# QED_2550_dos_caras.net
KiCad netlist of a schematic drawn in EAGLE
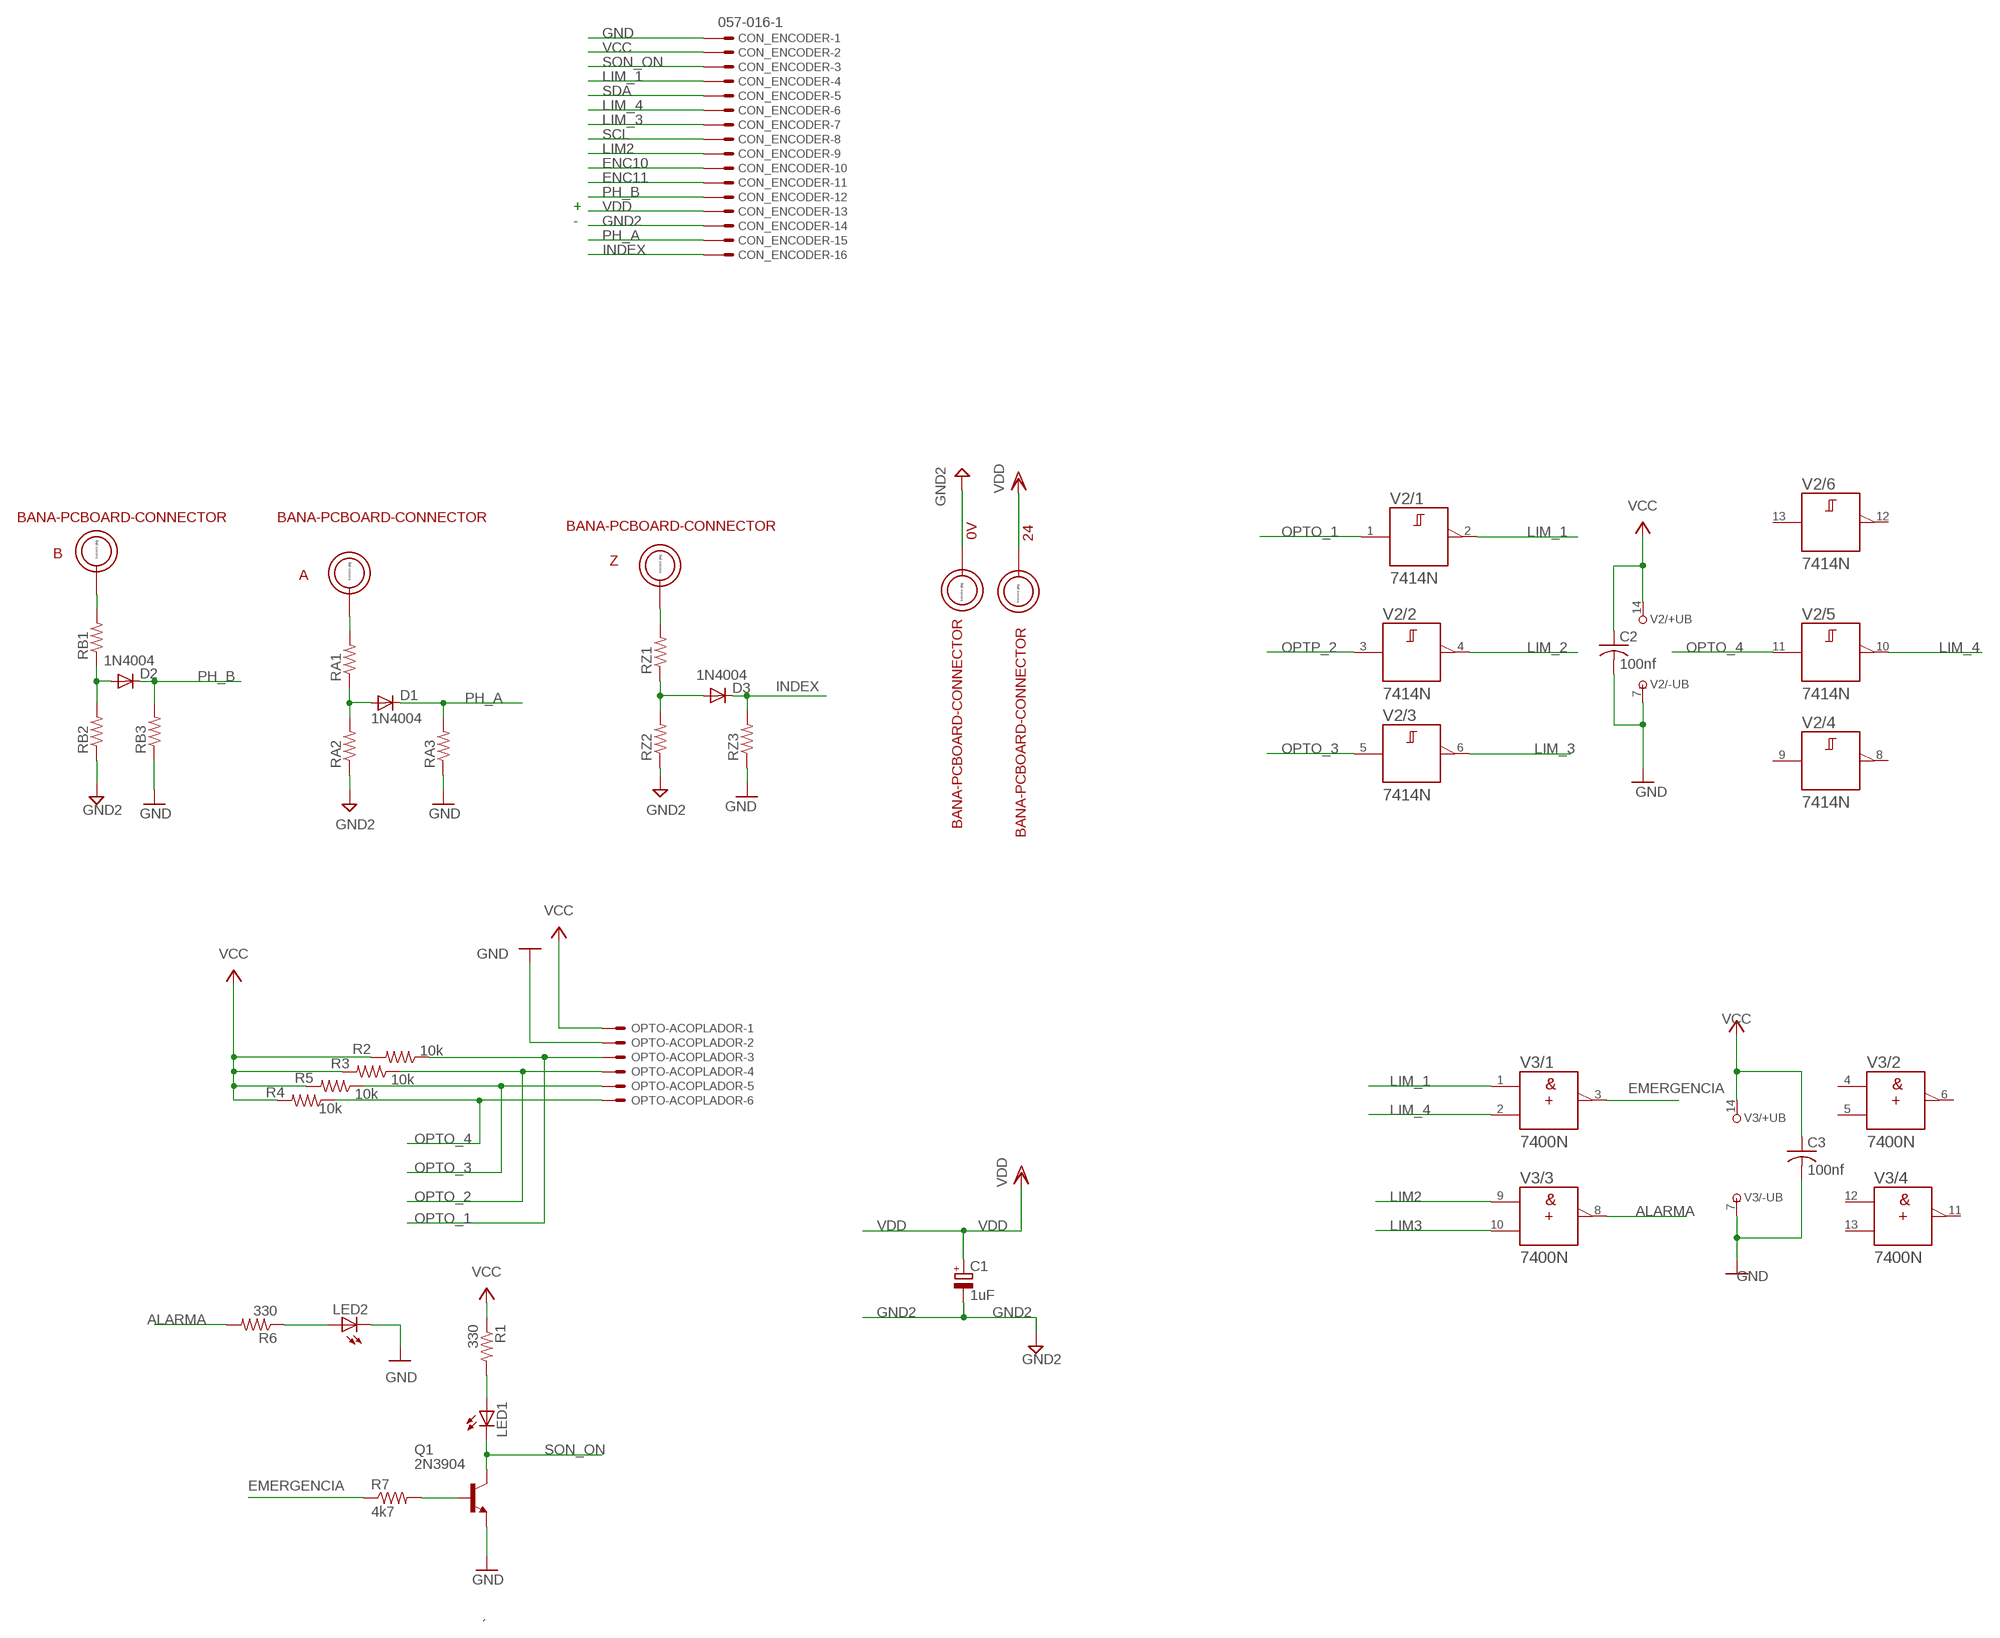
[diagram p0: schematic, sheet 1]

(export (version "E")
  (design (tool "Eeschema 10.0.6"))
  (components
    (comp (ref "0V")
      (value "BANA-PCBOARD-CONNECTOR")
      (footprint "eagle-import:BANA_PLUG")
      (libsource (lib "eagle-import") (part "BANA-PCBOARD-CONNECTOR"))
    )
    (comp (ref "24")
      (value "BANA-PCBOARD-CONNECTOR")
      (footprint "eagle-import:BANA_PLUG")
      (libsource (lib "eagle-import") (part "BANA-PCBOARD-CONNECTOR"))
    )
    (comp (ref "A")
      (value "BANA-PCBOARD-CONNECTOR")
      (footprint "eagle-import:BANA_PLUG")
      (libsource (lib "eagle-import") (part "BANA-PCBOARD-CONNECTOR"))
    )
    (comp (ref "B")
      (value "BANA-PCBOARD-CONNECTOR")
      (footprint "eagle-import:BANA_PLUG")
      (libsource (lib "eagle-import") (part "BANA-PCBOARD-CONNECTOR"))
    )
    (comp (ref "C1")
      (value "1uF")
      (footprint "eagle-import:E2,5-6")
      (libsource (lib "eagle-import") (part "CPOL-EUE2.5-6"))
    )
    (comp (ref "C2")
      (value "100nf")
      (footprint "eagle-import:C025-024X044")
      (libsource (lib "eagle-import") (part "C-US025-024X044"))
    )
    (comp (ref "C3")
      (value "100nf")
      (footprint "eagle-import:C025-024X044")
      (libsource (lib "eagle-import") (part "C-US025-024X044"))
    )
    (comp (ref "CON_ENCODER")
      (value "057-016-1")
      (footprint "eagle-import:057-016-1")
      (libsource (lib "eagle-import") (part "057-016-1"))
    )
    (comp (ref "D1")
      (value "1N4004")
      (footprint "eagle-import:DO41-10")
      (libsource (lib "eagle-import") (part "1N4004"))
    )
    (comp (ref "D2")
      (value "1N4004")
      (footprint "eagle-import:DO41-10")
      (libsource (lib "eagle-import") (part "1N4004"))
    )
    (comp (ref "D3")
      (value "1N4004")
      (footprint "eagle-import:DO41-10")
      (libsource (lib "eagle-import") (part "1N4004"))
    )
    (comp (ref "LED1")
      (value "LED5MM")
      (footprint "eagle-import:LED5MM")
      (libsource (lib "eagle-import") (part "LED5MM"))
    )
    (comp (ref "LED2")
      (value "LED5MM")
      (footprint "eagle-import:LED5MM")
      (libsource (lib "eagle-import") (part "LED5MM"))
    )
    (comp (ref "OPTO-ACOPLADOR")
      (value "22-23-2061")
      (footprint "eagle-import:22-23-2061")
      (fields (field (name "MF") "MOLEX"))
      (libsource (lib "eagle-import") (part "22-23-2061"))
    )
    (comp (ref "Q1")
      (value "2N3904")
      (footprint "eagle-import:TO92")
      (libsource (lib "eagle-import") (part "2N3904"))
    )
    (comp (ref "R1")
      (value "330")
      (footprint "eagle-import:0204_7")
      (libsource (lib "eagle-import") (part "R-US_0204/7"))
    )
    (comp (ref "R2")
      (value "10k")
      (footprint "eagle-import:0204_7")
      (libsource (lib "eagle-import") (part "R-US_0204/7"))
    )
    (comp (ref "R3")
      (value "10k")
      (footprint "eagle-import:0204_7")
      (libsource (lib "eagle-import") (part "R-US_0204/7"))
    )
    (comp (ref "R4")
      (value "10k")
      (footprint "eagle-import:0204_7")
      (libsource (lib "eagle-import") (part "R-US_0204/7"))
    )
    (comp (ref "R5")
      (value "10k")
      (footprint "eagle-import:0204_7")
      (libsource (lib "eagle-import") (part "R-US_0204/7"))
    )
    (comp (ref "R6")
      (value "330")
      (footprint "eagle-import:0204_7")
      (libsource (lib "eagle-import") (part "R-US_0204/7"))
    )
    (comp (ref "R7")
      (value "4k7")
      (footprint "eagle-import:0204_7")
      (libsource (lib "eagle-import") (part "R-US_0204/7"))
    )
    (comp (ref "RA1")
      (value "R-US_0204/7")
      (footprint "eagle-import:0204_7")
      (libsource (lib "eagle-import") (part "R-US_0204/7"))
    )
    (comp (ref "RA2")
      (value "R-US_0204/7")
      (footprint "eagle-import:0204_7")
      (libsource (lib "eagle-import") (part "R-US_0204/7"))
    )
    (comp (ref "RA3")
      (value "R-US_0204/7")
      (footprint "eagle-import:0204_7")
      (libsource (lib "eagle-import") (part "R-US_0204/7"))
    )
    (comp (ref "RB1")
      (value "R-US_0204/7")
      (footprint "eagle-import:0204_7")
      (libsource (lib "eagle-import") (part "R-US_0204/7"))
    )
    (comp (ref "RB2")
      (value "R-US_0204/7")
      (footprint "eagle-import:0204_7")
      (libsource (lib "eagle-import") (part "R-US_0204/7"))
    )
    (comp (ref "RB3")
      (value "R-US_0204/7")
      (footprint "eagle-import:0204_7")
      (libsource (lib "eagle-import") (part "R-US_0204/7"))
    )
    (comp (ref "RZ1")
      (value "R-US_0204/7")
      (footprint "eagle-import:0204_7")
      (libsource (lib "eagle-import") (part "R-US_0204/7"))
    )
    (comp (ref "RZ2")
      (value "R-US_0204/7")
      (footprint "eagle-import:0204_7")
      (libsource (lib "eagle-import") (part "R-US_0204/7"))
    )
    (comp (ref "RZ3")
      (value "R-US_0204/7")
      (footprint "eagle-import:0204_7")
      (libsource (lib "eagle-import") (part "R-US_0204/7"))
    )
    (comp (ref "V2")
      (value "7414N")
      (footprint "eagle-import:DIL14")
      (libsource (lib "eagle-import") (part "7414N"))
    )
    (comp (ref "V3")
      (value "7400N")
      (footprint "eagle-import:DIL14")
      (libsource (lib "eagle-import") (part "7400N"))
    )
    (comp (ref "Z")
      (value "BANA-PCBOARD-CONNECTOR")
      (footprint "eagle-import:BANA_PLUG")
      (libsource (lib "eagle-import") (part "BANA-PCBOARD-CONNECTOR"))
    )
  )
  (nets
    (net (code "1") (name "/ALARMA") (class "Default")
      (node (ref "R6") (pin "2") (pinfunction "2_2") (pintype "passive"))
      (node (ref "V3") (pin "8") (pinfunction "Y_8") (pintype "output"))
    )
    (net (code "2") (name "/EMERGENCIA") (class "Default")
      (node (ref "R7") (pin "1") (pinfunction "1_1") (pintype "passive"))
      (node (ref "V3") (pin "3") (pinfunction "Y_3") (pintype "output"))
    )
    (net (code "3") (name "/ENC10") (class "Default")
      (node (ref "CON_ENCODER") (pin "10") (pinfunction "S_10") (pintype "passive"))
    )
    (net (code "4") (name "/ENC11") (class "Default")
      (node (ref "CON_ENCODER") (pin "11") (pinfunction "S_11") (pintype "passive"))
    )
    (net (code "5") (name "/INDEX") (class "Default")
      (node (ref "CON_ENCODER") (pin "16") (pinfunction "S_16") (pintype "passive"))
      (node (ref "D3") (pin "C") (pinfunction "C_C") (pintype "passive"))
      (node (ref "RZ3") (pin "2") (pinfunction "2_2") (pintype "passive"))
    )
    (net (code "6") (name "/LIM2") (class "Default")
      (node (ref "CON_ENCODER") (pin "9") (pinfunction "S_9") (pintype "passive"))
      (node (ref "V3") (pin "9") (pinfunction "A_9") (pintype "input"))
    )
    (net (code "7") (name "/LIM3") (class "Default")
      (node (ref "V3") (pin "10") (pinfunction "B_10") (pintype "input"))
    )
    (net (code "8") (name "/LIM_1") (class "Default")
      (node (ref "CON_ENCODER") (pin "4") (pinfunction "S_4") (pintype "passive"))
      (node (ref "V2") (pin "2") (pinfunction "Y_2") (pintype "output"))
      (node (ref "V3") (pin "1") (pinfunction "A_1") (pintype "input"))
    )
    (net (code "9") (name "/LIM_2") (class "Default")
      (node (ref "V2") (pin "4") (pinfunction "Y_4") (pintype "output"))
    )
    (net (code "10") (name "/LIM_3") (class "Default")
      (node (ref "CON_ENCODER") (pin "7") (pinfunction "S_7") (pintype "passive"))
      (node (ref "V2") (pin "6") (pinfunction "Y_6") (pintype "output"))
    )
    (net (code "11") (name "/LIM_4") (class "Default")
      (node (ref "CON_ENCODER") (pin "6") (pinfunction "S_6") (pintype "passive"))
      (node (ref "V2") (pin "10") (pinfunction "Y_10") (pintype "output"))
      (node (ref "V3") (pin "2") (pinfunction "B_2") (pintype "input"))
    )
    (net (code "12") (name "/OPTO_1") (class "Default")
      (node (ref "OPTO-ACOPLADOR") (pin "3") (pinfunction "S_3") (pintype "passive"))
      (node (ref "R2") (pin "1") (pinfunction "1_1") (pintype "passive"))
      (node (ref "V2") (pin "1") (pinfunction "A_1") (pintype "input"))
    )
    (net (code "13") (name "/OPTO_2") (class "Default")
      (node (ref "OPTO-ACOPLADOR") (pin "4") (pinfunction "S_4") (pintype "passive"))
      (node (ref "R3") (pin "1") (pinfunction "1_1") (pintype "passive"))
    )
    (net (code "14") (name "/OPTO_3") (class "Default")
      (node (ref "OPTO-ACOPLADOR") (pin "5") (pinfunction "S_5") (pintype "passive"))
      (node (ref "R5") (pin "1") (pinfunction "1_1") (pintype "passive"))
      (node (ref "V2") (pin "5") (pinfunction "A_5") (pintype "input"))
    )
    (net (code "15") (name "/OPTO_4") (class "Default")
      (node (ref "OPTO-ACOPLADOR") (pin "6") (pinfunction "S_6") (pintype "passive"))
      (node (ref "R4") (pin "1") (pinfunction "1_1") (pintype "passive"))
      (node (ref "V2") (pin "11") (pinfunction "A_11") (pintype "input"))
    )
    (net (code "16") (name "/OPTP_2") (class "Default")
      (node (ref "V2") (pin "3") (pinfunction "A_3") (pintype "input"))
    )
    (net (code "17") (name "/PH_A") (class "Default")
      (node (ref "CON_ENCODER") (pin "15") (pinfunction "S_15") (pintype "passive"))
      (node (ref "D1") (pin "C") (pinfunction "C_C") (pintype "passive"))
      (node (ref "RA3") (pin "2") (pinfunction "2_2") (pintype "passive"))
    )
    (net (code "18") (name "/PH_B") (class "Default")
      (node (ref "CON_ENCODER") (pin "12") (pinfunction "S_12") (pintype "passive"))
      (node (ref "D2") (pin "C") (pinfunction "C_C") (pintype "passive"))
      (node (ref "RB3") (pin "2") (pinfunction "2_2") (pintype "passive"))
    )
    (net (code "19") (name "/SCL") (class "Default")
      (node (ref "CON_ENCODER") (pin "8") (pinfunction "S_8") (pintype "passive"))
    )
    (net (code "20") (name "/SDA") (class "Default")
      (node (ref "CON_ENCODER") (pin "5") (pinfunction "S_5") (pintype "passive"))
    )
    (net (code "21") (name "/SON_ON") (class "Default")
      (node (ref "CON_ENCODER") (pin "3") (pinfunction "S_3") (pintype "passive"))
      (node (ref "LED1") (pin "K") (pinfunction "C_K") (pintype "passive"))
      (node (ref "Q1") (pin "1") (pinfunction "C_1") (pintype "passive"))
    )
    (net (code "22") (name "GND") (class "Default")
      (node (ref "C2") (pin "2") (pinfunction "2_2") (pintype "passive"))
      (node (ref "C3") (pin "2") (pinfunction "2_2") (pintype "passive"))
      (node (ref "CON_ENCODER") (pin "1") (pinfunction "S_1") (pintype "passive"))
      (node (ref "LED2") (pin "K") (pinfunction "C_K") (pintype "passive"))
      (node (ref "OPTO-ACOPLADOR") (pin "2") (pinfunction "S_2") (pintype "passive"))
      (node (ref "Q1") (pin "3") (pinfunction "E_3") (pintype "passive"))
      (node (ref "RA3") (pin "1") (pinfunction "1_1") (pintype "passive"))
      (node (ref "RB3") (pin "1") (pinfunction "1_1") (pintype "passive"))
      (node (ref "RZ3") (pin "1") (pinfunction "1_1") (pintype "passive"))
      (node (ref "V2") (pin "7") (pinfunction "-UB_7") (pintype "power_in"))
      (node (ref "V3") (pin "7") (pinfunction "-UB_7") (pintype "power_in"))
    )
    (net (code "23") (name "GND2") (class "Default")
      (node (ref "0V") (pin "P$1") (pinfunction "P$1_P$1") (pintype "bidirectional"))
      (node (ref "C1") (pin "-") (pinfunction "-_-") (pintype "passive"))
      (node (ref "CON_ENCODER") (pin "14") (pinfunction "S_14") (pintype "passive"))
      (node (ref "RA2") (pin "1") (pinfunction "1_1") (pintype "passive"))
      (node (ref "RB2") (pin "1") (pinfunction "1_1") (pintype "passive"))
      (node (ref "RZ2") (pin "1") (pinfunction "1_1") (pintype "passive"))
    )
    (net (code "24") (name "Net-(A-PadP$1)") (class "Default")
      (node (ref "A") (pin "P$1") (pinfunction "P$1_P$1") (pintype "bidirectional"))
      (node (ref "RA1") (pin "2") (pinfunction "2_2") (pintype "passive"))
    )
    (net (code "25") (name "Net-(B-PadP$1)") (class "Default")
      (node (ref "B") (pin "P$1") (pinfunction "P$1_P$1") (pintype "bidirectional"))
      (node (ref "RB1") (pin "2") (pinfunction "2_2") (pintype "passive"))
    )
    (net (code "26") (name "Net-(D1-PadA)") (class "Default")
      (node (ref "D1") (pin "A") (pinfunction "A_A") (pintype "passive"))
      (node (ref "RA1") (pin "1") (pinfunction "1_1") (pintype "passive"))
      (node (ref "RA2") (pin "2") (pinfunction "2_2") (pintype "passive"))
    )
    (net (code "27") (name "Net-(D2-PadA)") (class "Default")
      (node (ref "D2") (pin "A") (pinfunction "A_A") (pintype "passive"))
      (node (ref "RB1") (pin "1") (pinfunction "1_1") (pintype "passive"))
      (node (ref "RB2") (pin "2") (pinfunction "2_2") (pintype "passive"))
    )
    (net (code "28") (name "Net-(D3-PadA)") (class "Default")
      (node (ref "D3") (pin "A") (pinfunction "A_A") (pintype "passive"))
      (node (ref "RZ1") (pin "1") (pinfunction "1_1") (pintype "passive"))
      (node (ref "RZ2") (pin "2") (pinfunction "2_2") (pintype "passive"))
    )
    (net (code "29") (name "Net-(LED1-PadA)") (class "Default")
      (node (ref "LED1") (pin "A") (pinfunction "A_A") (pintype "passive"))
      (node (ref "R1") (pin "2") (pinfunction "2_2") (pintype "passive"))
    )
    (net (code "30") (name "Net-(LED2-PadA)") (class "Default")
      (node (ref "LED2") (pin "A") (pinfunction "A_A") (pintype "passive"))
      (node (ref "R6") (pin "1") (pinfunction "1_1") (pintype "passive"))
    )
    (net (code "31") (name "Net-(Q1-B)") (class "Default")
      (node (ref "Q1") (pin "2") (pinfunction "B_2") (pintype "passive"))
      (node (ref "R7") (pin "2") (pinfunction "2_2") (pintype "passive"))
    )
    (net (code "32") (name "Net-(RZ1-Pad2)") (class "Default")
      (node (ref "RZ1") (pin "2") (pinfunction "2_2") (pintype "passive"))
      (node (ref "Z") (pin "P$1") (pinfunction "P$1_P$1") (pintype "bidirectional"))
    )
    (net (code "33") (name "VCC") (class "Default")
      (node (ref "C2") (pin "1") (pinfunction "1_1") (pintype "passive"))
      (node (ref "C3") (pin "1") (pinfunction "1_1") (pintype "passive"))
      (node (ref "CON_ENCODER") (pin "2") (pinfunction "S_2") (pintype "passive"))
      (node (ref "OPTO-ACOPLADOR") (pin "1") (pinfunction "S_1") (pintype "passive"))
      (node (ref "R1") (pin "1") (pinfunction "1_1") (pintype "passive"))
      (node (ref "R2") (pin "2") (pinfunction "2_2") (pintype "passive"))
      (node (ref "R3") (pin "2") (pinfunction "2_2") (pintype "passive"))
      (node (ref "R4") (pin "2") (pinfunction "2_2") (pintype "passive"))
      (node (ref "R5") (pin "2") (pinfunction "2_2") (pintype "passive"))
      (node (ref "V2") (pin "14") (pinfunction "+UB_14") (pintype "power_in"))
      (node (ref "V3") (pin "14") (pinfunction "+UB_14") (pintype "power_in"))
    )
    (net (code "34") (name "VDD") (class "Default")
      (node (ref "24") (pin "P$1") (pinfunction "P$1_P$1") (pintype "bidirectional"))
      (node (ref "C1") (pin "+") (pinfunction "+_+") (pintype "passive"))
      (node (ref "CON_ENCODER") (pin "13") (pinfunction "S_13") (pintype "passive"))
    )
    (net (code "35") (name "unconnected-(V2F-A-Pad9)") (class "Default")
      (node (ref "V2") (pin "9") (pinfunction "A_9") (pintype "input"))
    )
    (net (code "36") (name "unconnected-(V2F-Y-Pad8)") (class "Default")
      (node (ref "V2") (pin "8") (pinfunction "Y_8") (pintype "output"))
    )
    (net (code "37") (name "unconnected-(V2H-A-Pad13)") (class "Default")
      (node (ref "V2") (pin "13") (pinfunction "A_13") (pintype "input"))
    )
    (net (code "38") (name "unconnected-(V2H-Y-Pad12)") (class "Default")
      (node (ref "V2") (pin "12") (pinfunction "Y_12") (pintype "output"))
    )
    (net (code "39") (name "unconnected-(V3D-A-Pad4)") (class "Default")
      (node (ref "V3") (pin "4") (pinfunction "A_4") (pintype "input"))
    )
    (net (code "40") (name "unconnected-(V3D-B-Pad5)") (class "Default")
      (node (ref "V3") (pin "5") (pinfunction "B_5") (pintype "input"))
    )
    (net (code "41") (name "unconnected-(V3D-Y-Pad6)") (class "Default")
      (node (ref "V3") (pin "6") (pinfunction "Y_6") (pintype "output"))
    )
    (net (code "42") (name "unconnected-(V3F-A-Pad12)") (class "Default")
      (node (ref "V3") (pin "12") (pinfunction "A_12") (pintype "input"))
    )
    (net (code "43") (name "unconnected-(V3F-B-Pad13)") (class "Default")
      (node (ref "V3") (pin "13") (pinfunction "B_13") (pintype "input"))
    )
    (net (code "44") (name "unconnected-(V3F-Y-Pad11)") (class "Default")
      (node (ref "V3") (pin "11") (pinfunction "Y_11") (pintype "output"))
    )
  )
)
